# Main_Board.net
KiCad netlist of a schematic drawn in EAGLE
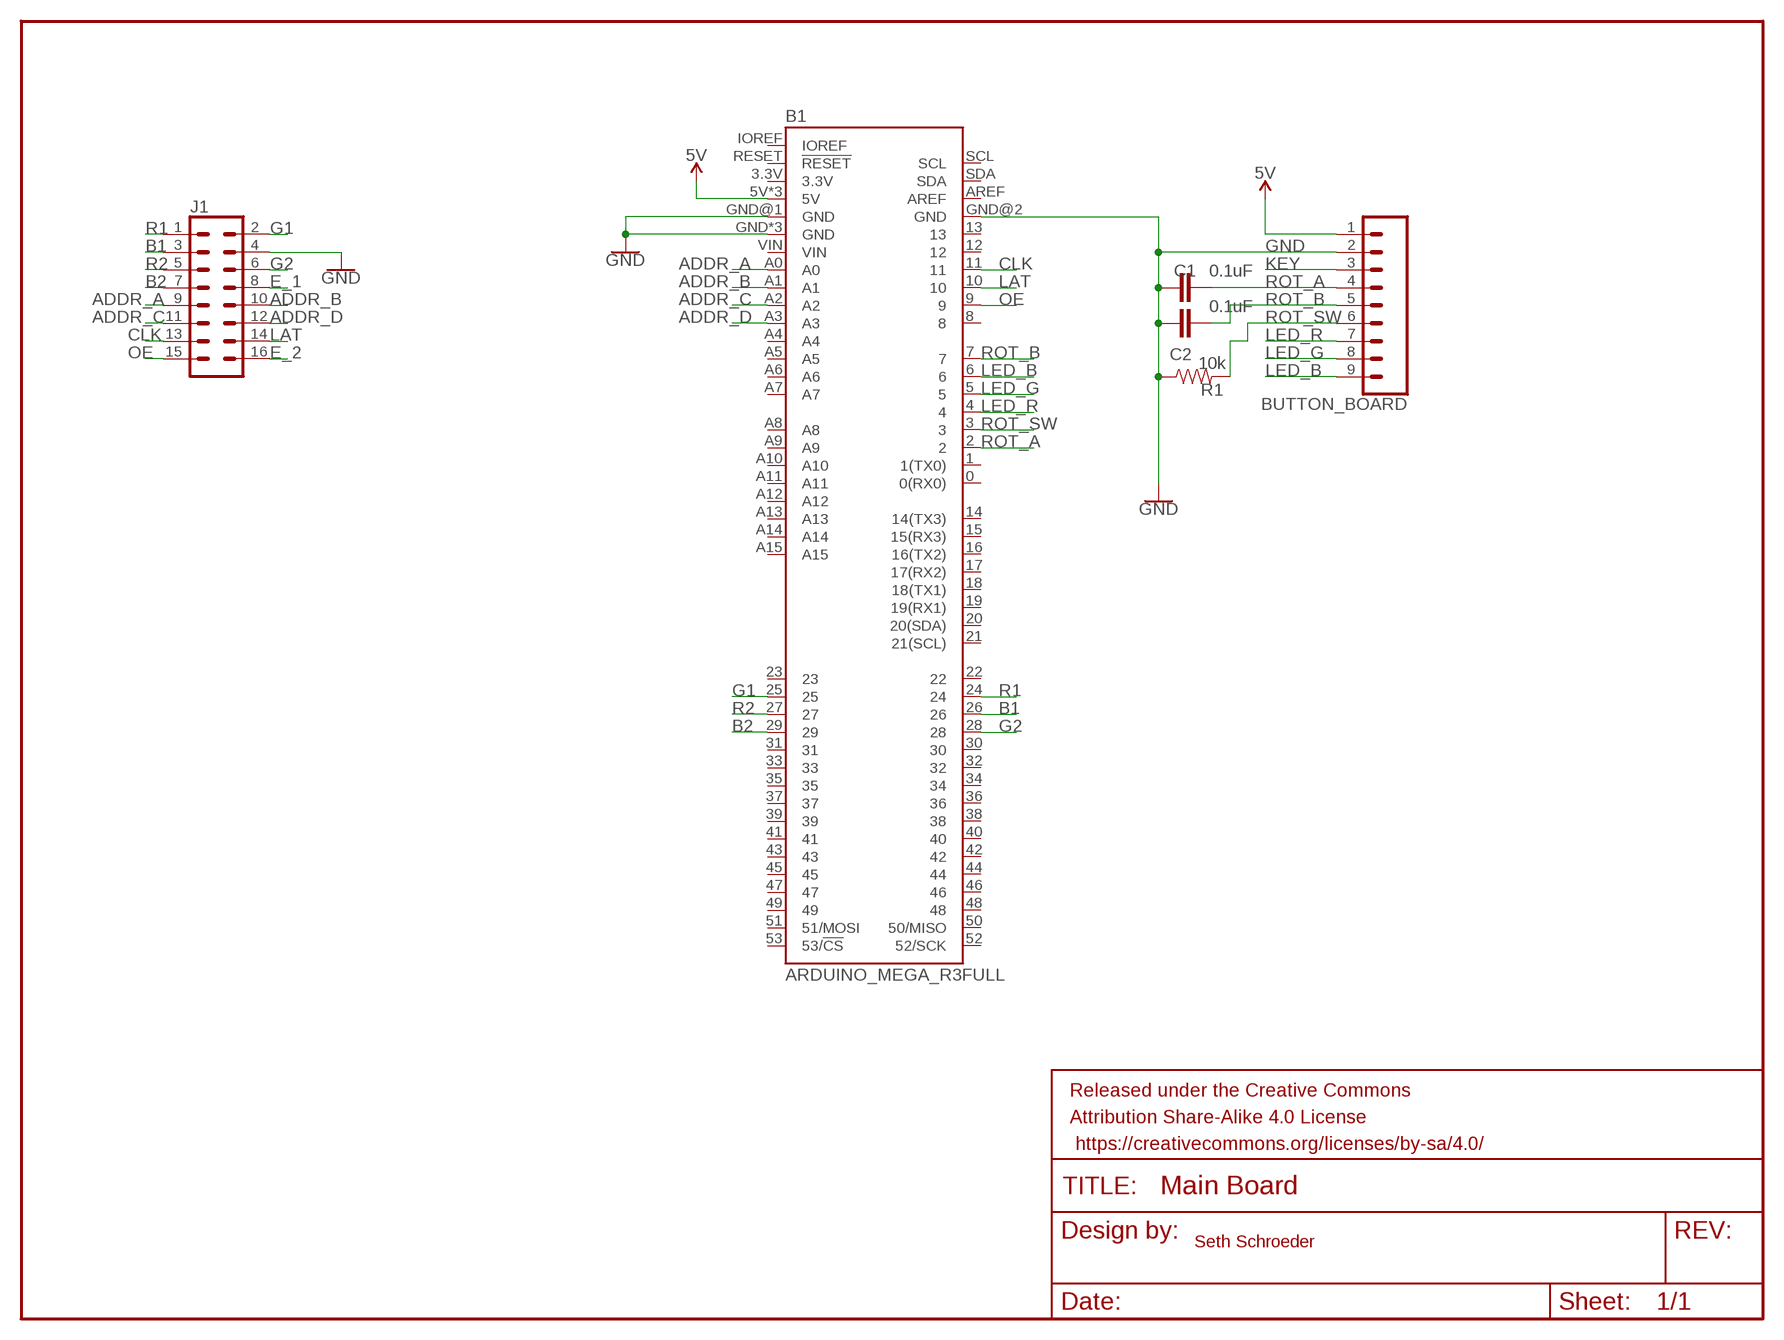
[diagram p0: schematic, sheet 1]

(export (version "E")
  (design (tool "Eeschema 10.0.6"))
  (components
    (comp (ref "B1")
      (value "ARDUINO_MEGA_R3FULL")
      (footprint "eagle-import:ARDUINO_MEGA_NO_SILK")
      (libsource (lib "eagle-import") (part "ARDUINO_MEGA_R3FULL"))
    )
    (comp (ref "BUTTON_BOARD")
      (value "CONN_09")
      (footprint "eagle-import:1X09")
      (libsource (lib "eagle-import") (part "CONN_09"))
    )
    (comp (ref "C1")
      (value "0.1uF")
      (footprint "eagle-import:CAP-PTH-SMALL-KIT")
      (libsource (lib "eagle-import") (part "0.1UF-KIT-EZ-50V-20%"))
    )
    (comp (ref "C2")
      (value "0.1uF")
      (footprint "eagle-import:CAP-PTH-SMALL-KIT")
      (libsource (lib "eagle-import") (part "0.1UF-KIT-EZ-50V-20%"))
    )
    (comp (ref "FRAME1")
      (value "FRAME-LETTER")
      (footprint "eagle-import:CREATIVE_COMMONS")
      (libsource (lib "eagle-import") (part "FRAME-LETTER"))
    )
    (comp (ref "J1")
      (value "CONN_08X2_SHROUD")
      (footprint "eagle-import:2X8-SHROUDED_LOCK")
      (libsource (lib "eagle-import") (part "CONN_08X2_SHROUD"))
    )
    (comp (ref "R1")
      (value "10k")
      (footprint "eagle-import:AXIAL-0.3")
      (libsource (lib "eagle-import") (part "10KOHM-HORIZ-1/4W-1%"))
    )
  )
  (nets
    (net (code "1") (name "/ADDR_A") (class "Default")
      (node (ref "B1") (pin "A0") (pinfunction "A0_A0") (pintype "bidirectional"))
      (node (ref "J1") (pin "9") (pinfunction "9_9") (pintype "passive"))
    )
    (net (code "2") (name "/ADDR_B") (class "Default")
      (node (ref "B1") (pin "A1") (pinfunction "A1_A1") (pintype "bidirectional"))
      (node (ref "J1") (pin "10") (pinfunction "10_10") (pintype "passive"))
    )
    (net (code "3") (name "/ADDR_C") (class "Default")
      (node (ref "B1") (pin "A2") (pinfunction "A2_A2") (pintype "bidirectional"))
      (node (ref "J1") (pin "11") (pinfunction "11_11") (pintype "passive"))
    )
    (net (code "4") (name "/ADDR_D") (class "Default")
      (node (ref "B1") (pin "A3") (pinfunction "A3_A3") (pintype "bidirectional"))
      (node (ref "J1") (pin "12") (pinfunction "12_12") (pintype "passive"))
    )
    (net (code "5") (name "/B1") (class "Default")
      (node (ref "B1") (pin "26") (pinfunction "26_26") (pintype "bidirectional"))
      (node (ref "J1") (pin "3") (pinfunction "3_3") (pintype "passive"))
    )
    (net (code "6") (name "/B2") (class "Default")
      (node (ref "B1") (pin "29") (pinfunction "29_29") (pintype "bidirectional"))
      (node (ref "J1") (pin "7") (pinfunction "7_7") (pintype "passive"))
    )
    (net (code "7") (name "/CLK") (class "Default")
      (node (ref "B1") (pin "11") (pinfunction "11_11") (pintype "bidirectional"))
      (node (ref "J1") (pin "13") (pinfunction "13_13") (pintype "passive"))
    )
    (net (code "8") (name "/E_1") (class "Default")
      (node (ref "J1") (pin "8") (pinfunction "8_8") (pintype "passive"))
    )
    (net (code "9") (name "/E_2") (class "Default")
      (node (ref "J1") (pin "16") (pinfunction "16_16") (pintype "passive"))
    )
    (net (code "10") (name "/G1") (class "Default")
      (node (ref "B1") (pin "25") (pinfunction "25_25") (pintype "bidirectional"))
      (node (ref "J1") (pin "2") (pinfunction "2_2") (pintype "passive"))
    )
    (net (code "11") (name "/G2") (class "Default")
      (node (ref "B1") (pin "28") (pinfunction "28_28") (pintype "bidirectional"))
      (node (ref "J1") (pin "6") (pinfunction "6_6") (pintype "passive"))
    )
    (net (code "12") (name "/KEY") (class "Default")
      (node (ref "BUTTON_BOARD") (pin "3") (pinfunction "3_3") (pintype "passive"))
    )
    (net (code "13") (name "/LAT") (class "Default")
      (node (ref "B1") (pin "10") (pinfunction "10_10") (pintype "bidirectional"))
      (node (ref "J1") (pin "14") (pinfunction "14_14") (pintype "passive"))
    )
    (net (code "14") (name "/LED_B") (class "Default")
      (node (ref "B1") (pin "6") (pinfunction "6_6") (pintype "bidirectional"))
      (node (ref "BUTTON_BOARD") (pin "9") (pinfunction "9_9") (pintype "passive"))
    )
    (net (code "15") (name "/LED_G") (class "Default")
      (node (ref "B1") (pin "5") (pinfunction "5_5") (pintype "bidirectional"))
      (node (ref "BUTTON_BOARD") (pin "8") (pinfunction "8_8") (pintype "passive"))
    )
    (net (code "16") (name "/LED_R") (class "Default")
      (node (ref "B1") (pin "4") (pinfunction "4_4") (pintype "bidirectional"))
      (node (ref "BUTTON_BOARD") (pin "7") (pinfunction "7_7") (pintype "passive"))
    )
    (net (code "17") (name "/OE") (class "Default")
      (node (ref "B1") (pin "9") (pinfunction "9_9") (pintype "bidirectional"))
      (node (ref "J1") (pin "15") (pinfunction "15_15") (pintype "passive"))
    )
    (net (code "18") (name "/R1") (class "Default")
      (node (ref "B1") (pin "24") (pinfunction "24_24") (pintype "bidirectional"))
      (node (ref "J1") (pin "1") (pinfunction "1_1") (pintype "passive"))
    )
    (net (code "19") (name "/R2") (class "Default")
      (node (ref "B1") (pin "27") (pinfunction "27_27") (pintype "bidirectional"))
      (node (ref "J1") (pin "5") (pinfunction "5_5") (pintype "passive"))
    )
    (net (code "20") (name "/ROT_A") (class "Default")
      (node (ref "B1") (pin "2") (pinfunction "2_2") (pintype "bidirectional"))
      (node (ref "BUTTON_BOARD") (pin "4") (pinfunction "4_4") (pintype "passive"))
      (node (ref "C1") (pin "2") (pinfunction "2_2") (pintype "passive"))
    )
    (net (code "21") (name "/ROT_B") (class "Default")
      (node (ref "B1") (pin "7") (pinfunction "7_7") (pintype "bidirectional"))
      (node (ref "BUTTON_BOARD") (pin "5") (pinfunction "5_5") (pintype "passive"))
      (node (ref "C2") (pin "2") (pinfunction "2_2") (pintype "passive"))
    )
    (net (code "22") (name "/ROT_SW") (class "Default")
      (node (ref "B1") (pin "3") (pinfunction "3_3") (pintype "bidirectional"))
      (node (ref "BUTTON_BOARD") (pin "6") (pinfunction "6_6") (pintype "passive"))
      (node (ref "R1") (pin "P$2") (pinfunction "2_P$2") (pintype "passive"))
    )
    (net (code "23") (name "5V") (class "Default")
      (node (ref "B1") (pin "5V") (pinfunction "5V_5V") (pintype "bidirectional"))
      (node (ref "B1") (pin "5V@1") (pinfunction "5V_5V@1") (pintype "bidirectional"))
      (node (ref "B1") (pin "5V@2") (pinfunction "5V_5V@2") (pintype "bidirectional"))
      (node (ref "BUTTON_BOARD") (pin "1") (pinfunction "1_1") (pintype "passive"))
    )
    (net (code "24") (name "GND") (class "Default")
      (node (ref "B1") (pin "GND") (pinfunction "GND_GND") (pintype "bidirectional"))
      (node (ref "B1") (pin "GND@1") (pinfunction "GND_GND@1") (pintype "bidirectional"))
      (node (ref "B1") (pin "GND@2") (pinfunction "GND_GND@2") (pintype "bidirectional"))
      (node (ref "B1") (pin "GND@3") (pinfunction "GND_GND@3") (pintype "bidirectional"))
      (node (ref "B1") (pin "GND@4") (pinfunction "GND_GND@4") (pintype "bidirectional"))
      (node (ref "BUTTON_BOARD") (pin "2") (pinfunction "2_2") (pintype "passive"))
      (node (ref "C1") (pin "1") (pinfunction "1_1") (pintype "passive"))
      (node (ref "C2") (pin "1") (pinfunction "1_1") (pintype "passive"))
      (node (ref "J1") (pin "4") (pinfunction "4_4") (pintype "passive"))
      (node (ref "R1") (pin "P$1") (pinfunction "1_P$1") (pintype "passive"))
    )
    (net (code "25") (name "unconnected-(B1-0(RX0)-Pad0)") (class "Default")
      (node (ref "B1") (pin "0") (pinfunction "0(RX0)_0") (pintype "bidirectional"))
    )
    (net (code "26") (name "unconnected-(B1-1(TX0)-Pad1)") (class "Default")
      (node (ref "B1") (pin "1") (pinfunction "1(TX0)_1") (pintype "bidirectional"))
    )
    (net (code "27") (name "unconnected-(B1-14(TX3)-Pad14)") (class "Default")
      (node (ref "B1") (pin "14") (pinfunction "14(TX3)_14") (pintype "bidirectional"))
    )
    (net (code "28") (name "unconnected-(B1-15(RX3)-Pad15)") (class "Default")
      (node (ref "B1") (pin "15") (pinfunction "15(RX3)_15") (pintype "bidirectional"))
    )
    (net (code "29") (name "unconnected-(B1-16(TX2)-Pad16)") (class "Default")
      (node (ref "B1") (pin "16") (pinfunction "16(TX2)_16") (pintype "bidirectional"))
    )
    (net (code "30") (name "unconnected-(B1-17(RX2)-Pad17)") (class "Default")
      (node (ref "B1") (pin "17") (pinfunction "17(RX2)_17") (pintype "bidirectional"))
    )
    (net (code "31") (name "unconnected-(B1-18(TX1)-Pad18)") (class "Default")
      (node (ref "B1") (pin "18") (pinfunction "18(TX1)_18") (pintype "bidirectional"))
    )
    (net (code "32") (name "unconnected-(B1-19(RX1)-Pad19)") (class "Default")
      (node (ref "B1") (pin "19") (pinfunction "19(RX1)_19") (pintype "bidirectional"))
    )
    (net (code "33") (name "unconnected-(B1-20(SDA)-Pad20)") (class "Default")
      (node (ref "B1") (pin "20") (pinfunction "20(SDA)_20") (pintype "bidirectional"))
    )
    (net (code "34") (name "unconnected-(B1-21(SCL)-Pad21)") (class "Default")
      (node (ref "B1") (pin "21") (pinfunction "21(SCL)_21") (pintype "bidirectional"))
    )
    (net (code "35") (name "unconnected-(B1-50{slash}MISO-Pad50)") (class "Default")
      (node (ref "B1") (pin "50") (pinfunction "50/MISO_50") (pintype "bidirectional"))
    )
    (net (code "36") (name "unconnected-(B1-51{slash}MOSI-Pad51)") (class "Default")
      (node (ref "B1") (pin "51") (pinfunction "51/MOSI_51") (pintype "bidirectional"))
    )
    (net (code "37") (name "unconnected-(B1-52{slash}SCK-Pad52)") (class "Default")
      (node (ref "B1") (pin "52") (pinfunction "52/SCK_52") (pintype "bidirectional"))
    )
    (net (code "38") (name "unconnected-(B1-53{slash}~{CS}-Pad53)") (class "Default")
      (node (ref "B1") (pin "53") (pinfunction "53/~{CS}_53") (pintype "bidirectional"))
    )
    (net (code "39") (name "unconnected-(B1-Pad3.3V)") (class "Default")
      (node (ref "B1") (pin "3.3V") (pinfunction "3.3V_3.3V") (pintype "bidirectional"))
    )
    (net (code "40") (name "unconnected-(B1-Pad8)") (class "Default")
      (node (ref "B1") (pin "8") (pinfunction "8_8") (pintype "bidirectional"))
    )
    (net (code "41") (name "unconnected-(B1-Pad12)") (class "Default")
      (node (ref "B1") (pin "12") (pinfunction "12_12") (pintype "bidirectional"))
    )
    (net (code "42") (name "unconnected-(B1-Pad13)") (class "Default")
      (node (ref "B1") (pin "13") (pinfunction "13_13") (pintype "bidirectional"))
    )
    (net (code "43") (name "unconnected-(B1-Pad22)") (class "Default")
      (node (ref "B1") (pin "22") (pinfunction "22_22") (pintype "bidirectional"))
    )
    (net (code "44") (name "unconnected-(B1-Pad23)") (class "Default")
      (node (ref "B1") (pin "23") (pinfunction "23_23") (pintype "bidirectional"))
    )
    (net (code "45") (name "unconnected-(B1-Pad30)") (class "Default")
      (node (ref "B1") (pin "30") (pinfunction "30_30") (pintype "bidirectional"))
    )
    (net (code "46") (name "unconnected-(B1-Pad31)") (class "Default")
      (node (ref "B1") (pin "31") (pinfunction "31_31") (pintype "bidirectional"))
    )
    (net (code "47") (name "unconnected-(B1-Pad32)") (class "Default")
      (node (ref "B1") (pin "32") (pinfunction "32_32") (pintype "bidirectional"))
    )
    (net (code "48") (name "unconnected-(B1-Pad33)") (class "Default")
      (node (ref "B1") (pin "33") (pinfunction "33_33") (pintype "bidirectional"))
    )
    (net (code "49") (name "unconnected-(B1-Pad34)") (class "Default")
      (node (ref "B1") (pin "34") (pinfunction "34_34") (pintype "bidirectional"))
    )
    (net (code "50") (name "unconnected-(B1-Pad35)") (class "Default")
      (node (ref "B1") (pin "35") (pinfunction "35_35") (pintype "bidirectional"))
    )
    (net (code "51") (name "unconnected-(B1-Pad36)") (class "Default")
      (node (ref "B1") (pin "36") (pinfunction "36_36") (pintype "bidirectional"))
    )
    (net (code "52") (name "unconnected-(B1-Pad37)") (class "Default")
      (node (ref "B1") (pin "37") (pinfunction "37_37") (pintype "bidirectional"))
    )
    (net (code "53") (name "unconnected-(B1-Pad38)") (class "Default")
      (node (ref "B1") (pin "38") (pinfunction "38_38") (pintype "bidirectional"))
    )
    (net (code "54") (name "unconnected-(B1-Pad39)") (class "Default")
      (node (ref "B1") (pin "39") (pinfunction "39_39") (pintype "bidirectional"))
    )
    (net (code "55") (name "unconnected-(B1-Pad40)") (class "Default")
      (node (ref "B1") (pin "40") (pinfunction "40_40") (pintype "bidirectional"))
    )
    (net (code "56") (name "unconnected-(B1-Pad41)") (class "Default")
      (node (ref "B1") (pin "41") (pinfunction "41_41") (pintype "bidirectional"))
    )
    (net (code "57") (name "unconnected-(B1-Pad42)") (class "Default")
      (node (ref "B1") (pin "42") (pinfunction "42_42") (pintype "bidirectional"))
    )
    (net (code "58") (name "unconnected-(B1-Pad43)") (class "Default")
      (node (ref "B1") (pin "43") (pinfunction "43_43") (pintype "bidirectional"))
    )
    (net (code "59") (name "unconnected-(B1-Pad44)") (class "Default")
      (node (ref "B1") (pin "44") (pinfunction "44_44") (pintype "bidirectional"))
    )
    (net (code "60") (name "unconnected-(B1-Pad45)") (class "Default")
      (node (ref "B1") (pin "45") (pinfunction "45_45") (pintype "bidirectional"))
    )
    (net (code "61") (name "unconnected-(B1-Pad46)") (class "Default")
      (node (ref "B1") (pin "46") (pinfunction "46_46") (pintype "bidirectional"))
    )
    (net (code "62") (name "unconnected-(B1-Pad47)") (class "Default")
      (node (ref "B1") (pin "47") (pinfunction "47_47") (pintype "bidirectional"))
    )
    (net (code "63") (name "unconnected-(B1-Pad48)") (class "Default")
      (node (ref "B1") (pin "48") (pinfunction "48_48") (pintype "bidirectional"))
    )
    (net (code "64") (name "unconnected-(B1-Pad49)") (class "Default")
      (node (ref "B1") (pin "49") (pinfunction "49_49") (pintype "bidirectional"))
    )
    (net (code "65") (name "unconnected-(B1-PadA4)") (class "Default")
      (node (ref "B1") (pin "A4") (pinfunction "A4_A4") (pintype "bidirectional"))
    )
    (net (code "66") (name "unconnected-(B1-PadA5)") (class "Default")
      (node (ref "B1") (pin "A5") (pinfunction "A5_A5") (pintype "bidirectional"))
    )
    (net (code "67") (name "unconnected-(B1-PadA6)") (class "Default")
      (node (ref "B1") (pin "A6") (pinfunction "A6_A6") (pintype "bidirectional"))
    )
    (net (code "68") (name "unconnected-(B1-PadA7)") (class "Default")
      (node (ref "B1") (pin "A7") (pinfunction "A7_A7") (pintype "bidirectional"))
    )
    (net (code "69") (name "unconnected-(B1-PadA8)") (class "Default")
      (node (ref "B1") (pin "A8") (pinfunction "A8_A8") (pintype "bidirectional"))
    )
    (net (code "70") (name "unconnected-(B1-PadA9)") (class "Default")
      (node (ref "B1") (pin "A9") (pinfunction "A9_A9") (pintype "bidirectional"))
    )
    (net (code "71") (name "unconnected-(B1-PadA10)") (class "Default")
      (node (ref "B1") (pin "A10") (pinfunction "A10_A10") (pintype "bidirectional"))
    )
    (net (code "72") (name "unconnected-(B1-PadA11)") (class "Default")
      (node (ref "B1") (pin "A11") (pinfunction "A11_A11") (pintype "bidirectional"))
    )
    (net (code "73") (name "unconnected-(B1-PadA12)") (class "Default")
      (node (ref "B1") (pin "A12") (pinfunction "A12_A12") (pintype "bidirectional"))
    )
    (net (code "74") (name "unconnected-(B1-PadA13)") (class "Default")
      (node (ref "B1") (pin "A13") (pinfunction "A13_A13") (pintype "bidirectional"))
    )
    (net (code "75") (name "unconnected-(B1-PadA14)") (class "Default")
      (node (ref "B1") (pin "A14") (pinfunction "A14_A14") (pintype "bidirectional"))
    )
    (net (code "76") (name "unconnected-(B1-PadA15)") (class "Default")
      (node (ref "B1") (pin "A15") (pinfunction "A15_A15") (pintype "bidirectional"))
    )
    (net (code "77") (name "unconnected-(B1-PadAREF)") (class "Default")
      (node (ref "B1") (pin "AREF") (pinfunction "AREF_AREF") (pintype "bidirectional"))
    )
    (net (code "78") (name "unconnected-(B1-PadIOREF)") (class "Default")
      (node (ref "B1") (pin "IOREF") (pinfunction "IOREF_IOREF") (pintype "bidirectional"))
    )
    (net (code "79") (name "unconnected-(B1-PadSCL)") (class "Default")
      (node (ref "B1") (pin "SCL") (pinfunction "SCL_SCL") (pintype "bidirectional"))
    )
    (net (code "80") (name "unconnected-(B1-PadSDA)") (class "Default")
      (node (ref "B1") (pin "SDA") (pinfunction "SDA_SDA") (pintype "bidirectional"))
    )
    (net (code "81") (name "unconnected-(B1-PadVIN)") (class "Default")
      (node (ref "B1") (pin "VIN") (pinfunction "VIN_VIN") (pintype "bidirectional"))
    )
    (net (code "82") (name "unconnected-(B1-~{RESET}-PadRESET)") (class "Default")
      (node (ref "B1") (pin "RESET") (pinfunction "~{RESET}_RESET") (pintype "bidirectional"))
    )
  )
)
